# I.net
KiCad netlist of a schematic drawn in EAGLE
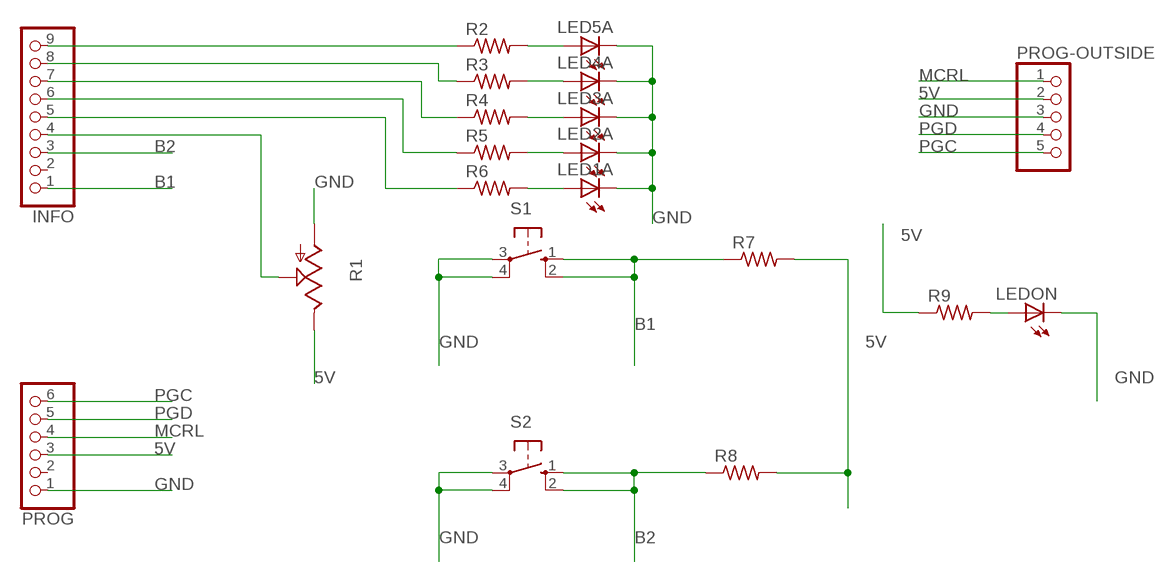
[diagram p0: schematic, sheet 1]

(export (version "E")
  (design (tool "Eeschema 10.0.6"))
  (components
    (comp (ref "INFO")
      (value "PINHD-1X9/90")
      (footprint "eagle-import:1X09_90")
      (libsource (lib "eagle-import") (part "PINHD-1X9/90"))
    )
    (comp (ref "LED1A")
      (value "LEDCHIPLED_1206")
      (footprint "eagle-import:CHIPLED_1206")
      (libsource (lib "eagle-import") (part "LEDCHIPLED_1206"))
    )
    (comp (ref "LED2A")
      (value "LEDCHIPLED_1206")
      (footprint "eagle-import:CHIPLED_1206")
      (libsource (lib "eagle-import") (part "LEDCHIPLED_1206"))
    )
    (comp (ref "LED3A")
      (value "LEDCHIPLED_1206")
      (footprint "eagle-import:CHIPLED_1206")
      (libsource (lib "eagle-import") (part "LEDCHIPLED_1206"))
    )
    (comp (ref "LED4A")
      (value "LEDCHIPLED_1206")
      (footprint "eagle-import:CHIPLED_1206")
      (libsource (lib "eagle-import") (part "LEDCHIPLED_1206"))
    )
    (comp (ref "LED5A")
      (value "LEDCHIPLED_1206")
      (footprint "eagle-import:CHIPLED_1206")
      (libsource (lib "eagle-import") (part "LEDCHIPLED_1206"))
    )
    (comp (ref "LEDON")
      (value "LEDCHIPLED_1206")
      (footprint "eagle-import:CHIPLED_1206")
      (libsource (lib "eagle-import") (part "LEDCHIPLED_1206"))
    )
    (comp (ref "PROG")
      (value "PINHD-1X6/90")
      (footprint "eagle-import:1X06_90")
      (libsource (lib "eagle-import") (part "PINHD-1X6/90"))
    )
    (comp (ref "PROG-OUTSIDE")
      (value "PINHD-1X5/90")
      (footprint "eagle-import:1X05_90")
      (libsource (lib "eagle-import") (part "PINHD-1X5/90"))
    )
    (comp (ref "R1")
      (value "TRIM_US-CA6V")
      (footprint "eagle-import:CA6V")
      (libsource (lib "eagle-import") (part "TRIM_US-CA6V"))
    )
    (comp (ref "R2")
      (value "R-US_M1206")
      (footprint "eagle-import:M1206")
      (libsource (lib "eagle-import") (part "R-US_M1206"))
    )
    (comp (ref "R3")
      (value "R-US_M1206")
      (footprint "eagle-import:M1206")
      (libsource (lib "eagle-import") (part "R-US_M1206"))
    )
    (comp (ref "R4")
      (value "R-US_M1206")
      (footprint "eagle-import:M1206")
      (libsource (lib "eagle-import") (part "R-US_M1206"))
    )
    (comp (ref "R5")
      (value "R-US_M1206")
      (footprint "eagle-import:M1206")
      (libsource (lib "eagle-import") (part "R-US_M1206"))
    )
    (comp (ref "R6")
      (value "R-US_M1206")
      (footprint "eagle-import:M1206")
      (libsource (lib "eagle-import") (part "R-US_M1206"))
    )
    (comp (ref "R7")
      (value "R-US_M1206")
      (footprint "eagle-import:M1206")
      (libsource (lib "eagle-import") (part "R-US_M1206"))
    )
    (comp (ref "R8")
      (value "R-US_M1206")
      (footprint "eagle-import:M1206")
      (libsource (lib "eagle-import") (part "R-US_M1206"))
    )
    (comp (ref "R9")
      (value "R-US_M1206")
      (footprint "eagle-import:M1206")
      (libsource (lib "eagle-import") (part "R-US_M1206"))
    )
    (comp (ref "S1")
      (value "10-XX")
      (footprint "eagle-import:B3F-10XX")
      (fields (field (name "MPN") "B3F-1000"))
      (libsource (lib "eagle-import") (part "10-XX"))
    )
    (comp (ref "S2")
      (value "10-XX")
      (footprint "eagle-import:B3F-10XX")
      (fields (field (name "MPN") "B3F-1000"))
      (libsource (lib "eagle-import") (part "10-XX"))
    )
  )
  (nets
    (net (code "1") (name "/5V") (class "Default")
      (node (ref "PROG") (pin "3") (pinfunction "3_3") (pintype "passive"))
      (node (ref "PROG-OUTSIDE") (pin "2") (pinfunction "2_2") (pintype "passive"))
      (node (ref "R1") (pin "E") (pinfunction "E_E") (pintype "passive"))
      (node (ref "R7") (pin "2") (pinfunction "2_2") (pintype "passive"))
      (node (ref "R8") (pin "2") (pinfunction "2_2") (pintype "passive"))
      (node (ref "R9") (pin "1") (pinfunction "1_1") (pintype "passive"))
    )
    (net (code "2") (name "/B1") (class "Default")
      (node (ref "INFO") (pin "1") (pinfunction "1_1") (pintype "passive"))
      (node (ref "R7") (pin "1") (pinfunction "1_1") (pintype "passive"))
      (node (ref "S1") (pin "1") (pinfunction "S_1") (pintype "passive"))
      (node (ref "S1") (pin "2") (pinfunction "S1_2") (pintype "passive"))
    )
    (net (code "3") (name "/B2") (class "Default")
      (node (ref "INFO") (pin "3") (pinfunction "3_3") (pintype "passive"))
      (node (ref "R8") (pin "1") (pinfunction "1_1") (pintype "passive"))
      (node (ref "S2") (pin "1") (pinfunction "S_1") (pintype "passive"))
      (node (ref "S2") (pin "2") (pinfunction "S1_2") (pintype "passive"))
    )
    (net (code "4") (name "/GND") (class "Default")
      (node (ref "LED1A") (pin "C") (pinfunction "C_C") (pintype "passive"))
      (node (ref "LED2A") (pin "C") (pinfunction "C_C") (pintype "passive"))
      (node (ref "LED3A") (pin "C") (pinfunction "C_C") (pintype "passive"))
      (node (ref "LED4A") (pin "C") (pinfunction "C_C") (pintype "passive"))
      (node (ref "LED5A") (pin "C") (pinfunction "C_C") (pintype "passive"))
      (node (ref "LEDON") (pin "C") (pinfunction "C_C") (pintype "passive"))
      (node (ref "PROG") (pin "1") (pinfunction "1_1") (pintype "passive"))
      (node (ref "PROG-OUTSIDE") (pin "3") (pinfunction "3_3") (pintype "passive"))
      (node (ref "R1") (pin "A") (pinfunction "A_A") (pintype "passive"))
      (node (ref "S1") (pin "3") (pinfunction "P_3") (pintype "passive"))
      (node (ref "S1") (pin "4") (pinfunction "P1_4") (pintype "passive"))
      (node (ref "S2") (pin "3") (pinfunction "P_3") (pintype "passive"))
      (node (ref "S2") (pin "4") (pinfunction "P1_4") (pintype "passive"))
    )
    (net (code "5") (name "/MCRL") (class "Default")
      (node (ref "PROG") (pin "4") (pinfunction "4_4") (pintype "passive"))
      (node (ref "PROG-OUTSIDE") (pin "1") (pinfunction "1_1") (pintype "passive"))
    )
    (net (code "6") (name "/PGC") (class "Default")
      (node (ref "PROG") (pin "6") (pinfunction "6_6") (pintype "passive"))
      (node (ref "PROG-OUTSIDE") (pin "5") (pinfunction "5_5") (pintype "passive"))
    )
    (net (code "7") (name "/PGD") (class "Default")
      (node (ref "PROG") (pin "5") (pinfunction "5_5") (pintype "passive"))
      (node (ref "PROG-OUTSIDE") (pin "4") (pinfunction "4_4") (pintype "passive"))
    )
    (net (code "8") (name "Net-(INFO-Pad4)") (class "Default")
      (node (ref "INFO") (pin "4") (pinfunction "4_4") (pintype "passive"))
      (node (ref "R1") (pin "S") (pinfunction "S_S") (pintype "passive"))
    )
    (net (code "9") (name "Net-(INFO-Pad5)") (class "Default")
      (node (ref "INFO") (pin "5") (pinfunction "5_5") (pintype "passive"))
      (node (ref "R6") (pin "1") (pinfunction "1_1") (pintype "passive"))
    )
    (net (code "10") (name "Net-(INFO-Pad6)") (class "Default")
      (node (ref "INFO") (pin "6") (pinfunction "6_6") (pintype "passive"))
      (node (ref "R5") (pin "1") (pinfunction "1_1") (pintype "passive"))
    )
    (net (code "11") (name "Net-(INFO-Pad7)") (class "Default")
      (node (ref "INFO") (pin "7") (pinfunction "7_7") (pintype "passive"))
      (node (ref "R4") (pin "1") (pinfunction "1_1") (pintype "passive"))
    )
    (net (code "12") (name "Net-(INFO-Pad8)") (class "Default")
      (node (ref "INFO") (pin "8") (pinfunction "8_8") (pintype "passive"))
      (node (ref "R3") (pin "1") (pinfunction "1_1") (pintype "passive"))
    )
    (net (code "13") (name "Net-(INFO-Pad9)") (class "Default")
      (node (ref "INFO") (pin "9") (pinfunction "9_9") (pintype "passive"))
      (node (ref "R2") (pin "1") (pinfunction "1_1") (pintype "passive"))
    )
    (net (code "14") (name "Net-(LED1A-PadA)") (class "Default")
      (node (ref "LED1A") (pin "A") (pinfunction "A_A") (pintype "passive"))
      (node (ref "R6") (pin "2") (pinfunction "2_2") (pintype "passive"))
    )
    (net (code "15") (name "Net-(LED2A-PadA)") (class "Default")
      (node (ref "LED2A") (pin "A") (pinfunction "A_A") (pintype "passive"))
      (node (ref "R5") (pin "2") (pinfunction "2_2") (pintype "passive"))
    )
    (net (code "16") (name "Net-(LED3A-PadA)") (class "Default")
      (node (ref "LED3A") (pin "A") (pinfunction "A_A") (pintype "passive"))
      (node (ref "R4") (pin "2") (pinfunction "2_2") (pintype "passive"))
    )
    (net (code "17") (name "Net-(LED4A-PadA)") (class "Default")
      (node (ref "LED4A") (pin "A") (pinfunction "A_A") (pintype "passive"))
      (node (ref "R3") (pin "2") (pinfunction "2_2") (pintype "passive"))
    )
    (net (code "18") (name "Net-(LED5A-PadA)") (class "Default")
      (node (ref "LED5A") (pin "A") (pinfunction "A_A") (pintype "passive"))
      (node (ref "R2") (pin "2") (pinfunction "2_2") (pintype "passive"))
    )
    (net (code "19") (name "Net-(LEDON-PadA)") (class "Default")
      (node (ref "LEDON") (pin "A") (pinfunction "A_A") (pintype "passive"))
      (node (ref "R9") (pin "2") (pinfunction "2_2") (pintype "passive"))
    )
    (net (code "20") (name "unconnected-(INFO-Pad2)") (class "Default")
      (node (ref "INFO") (pin "2") (pinfunction "2_2") (pintype "passive"))
    )
    (net (code "21") (name "unconnected-(PROG-Pad2)") (class "Default")
      (node (ref "PROG") (pin "2") (pinfunction "2_2") (pintype "passive"))
    )
  )
)
